# fc64x8.net
KiCad netlist of a schematic drawn in EAGLE
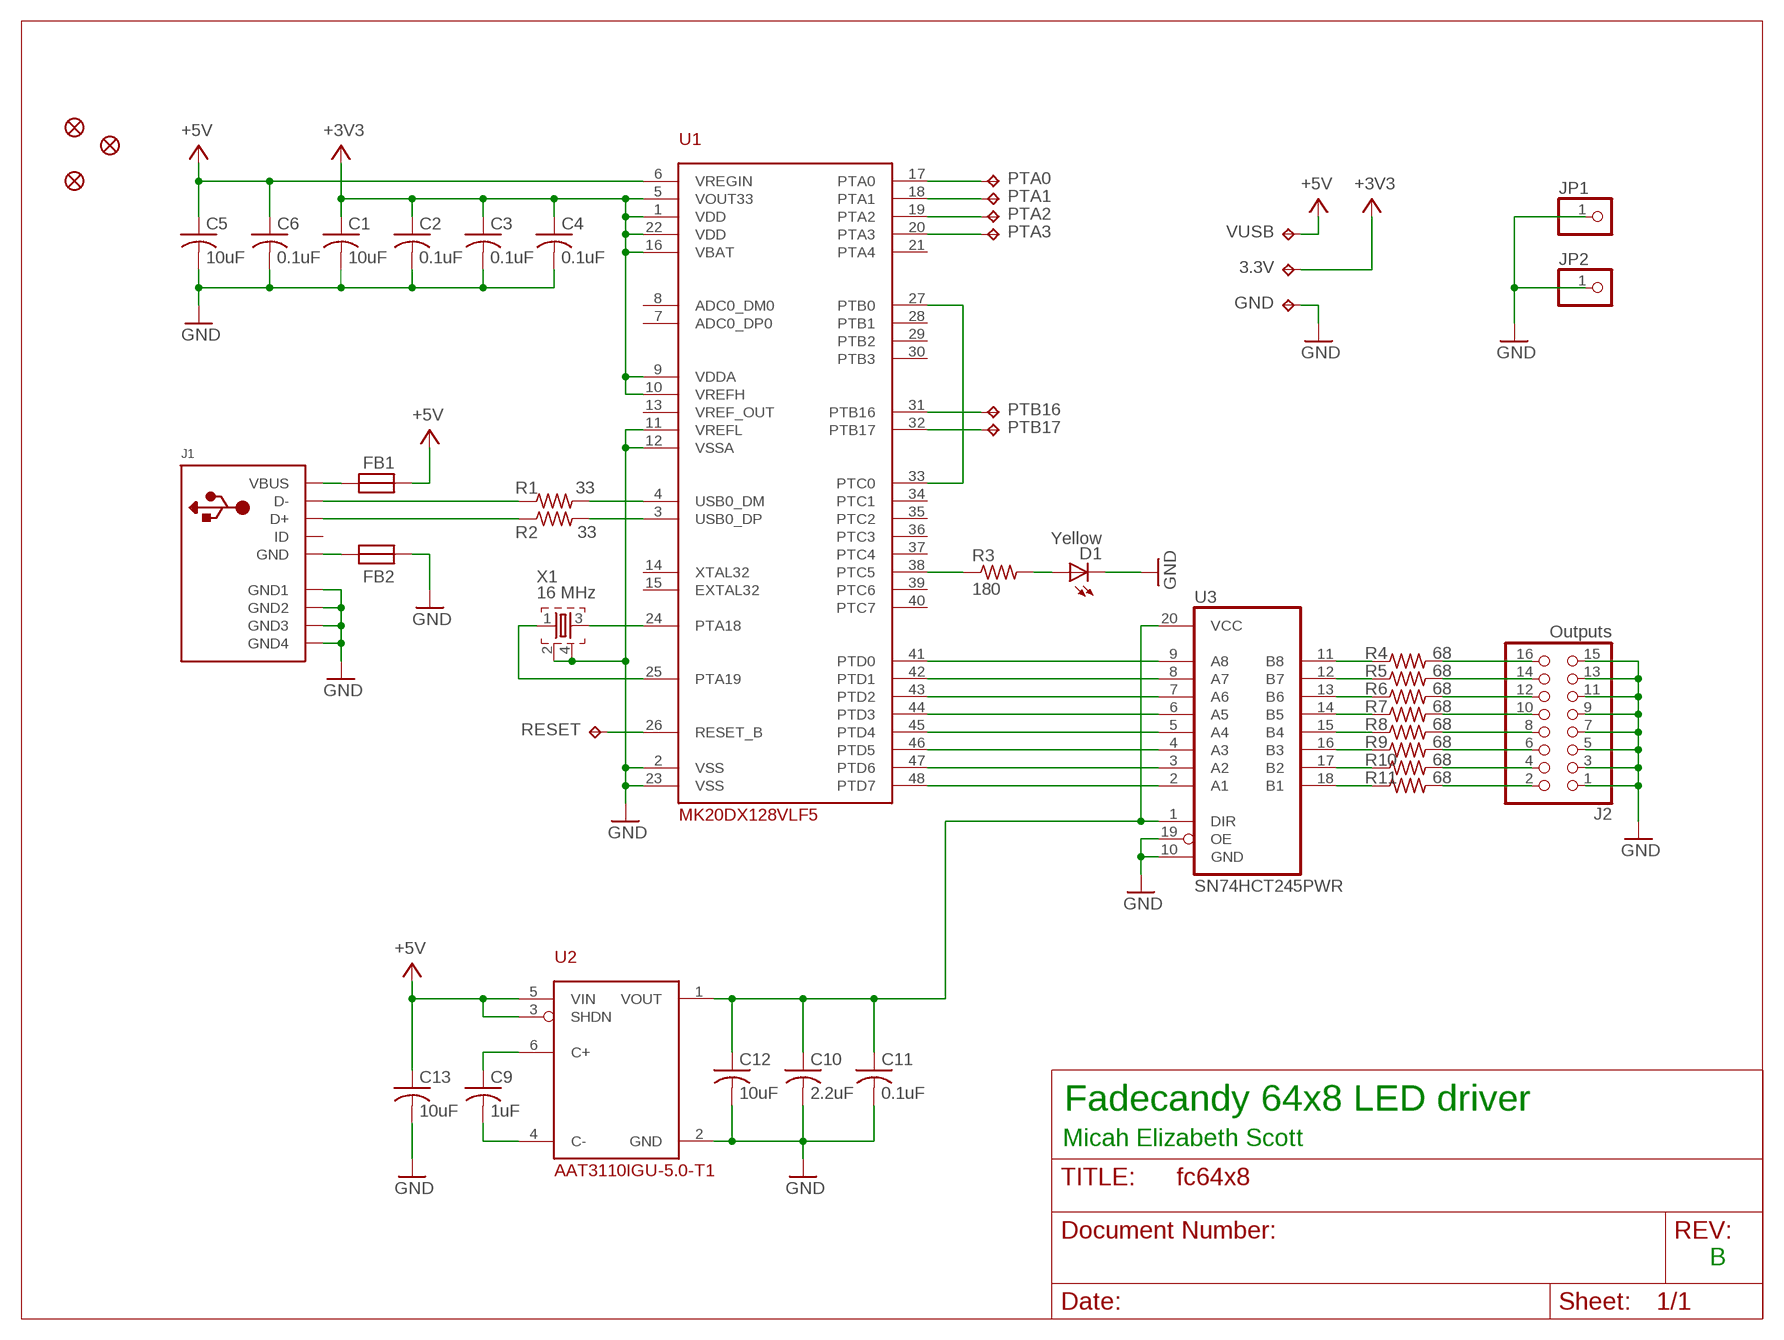
[diagram p0: schematic, sheet 1]

(export (version "E")
  (design (tool "Eeschema 10.0.6"))
  (components
    (comp (ref "3.3V")
      (value "TPTP18SQ")
      (footprint "eagle-import:TP18SQ")
      (libsource (lib "eagle-import") (part "TPTP18SQ"))
    )
    (comp (ref "C1")
      (value "10uF")
      (footprint "eagle-import:0805")
      (libsource (lib "eagle-import") (part "C-US0805/NO-OUTLINE"))
    )
    (comp (ref "C2")
      (value "0.1uF")
      (footprint "eagle-import:0805")
      (libsource (lib "eagle-import") (part "C-US0805/NO-OUTLINE"))
    )
    (comp (ref "C3")
      (value "0.1uF")
      (footprint "eagle-import:0805")
      (libsource (lib "eagle-import") (part "C-US0805/NO-OUTLINE"))
    )
    (comp (ref "C4")
      (value "0.1uF")
      (footprint "eagle-import:0805")
      (libsource (lib "eagle-import") (part "C-US0805/NO-OUTLINE"))
    )
    (comp (ref "C5")
      (value "10uF")
      (footprint "eagle-import:0805")
      (libsource (lib "eagle-import") (part "C-US0805/NO-OUTLINE"))
    )
    (comp (ref "C6")
      (value "0.1uF")
      (footprint "eagle-import:0805")
      (libsource (lib "eagle-import") (part "C-US0805/NO-OUTLINE"))
    )
    (comp (ref "C9")
      (value "1uF")
      (footprint "eagle-import:0805")
      (libsource (lib "eagle-import") (part "C-US0805/NO-OUTLINE"))
    )
    (comp (ref "C10")
      (value "2.2uF")
      (footprint "eagle-import:0805")
      (libsource (lib "eagle-import") (part "C-US0805/NO-OUTLINE"))
    )
    (comp (ref "C11")
      (value "0.1uF")
      (footprint "eagle-import:0805")
      (libsource (lib "eagle-import") (part "C-US0805/NO-OUTLINE"))
    )
    (comp (ref "C12")
      (value "10uF")
      (footprint "eagle-import:0805")
      (libsource (lib "eagle-import") (part "C-US0805/NO-OUTLINE"))
    )
    (comp (ref "C13")
      (value "10uF")
      (footprint "eagle-import:0805")
      (libsource (lib "eagle-import") (part "C-US0805/NO-OUTLINE"))
    )
    (comp (ref "D1")
      (value "Yellow")
      (footprint "eagle-import:CHIP-LED0805")
      (libsource (lib "eagle-import") (part "LEDCHIP-LED0805"))
    )
    (comp (ref "FB1")
      (value "FB0805/NO-OUTLINE")
      (footprint "eagle-import:0805")
      (libsource (lib "eagle-import") (part "FB0805/NO-OUTLINE"))
    )
    (comp (ref "FB2")
      (value "FB0805/NO-OUTLINE")
      (footprint "eagle-import:0805")
      (libsource (lib "eagle-import") (part "FB0805/NO-OUTLINE"))
    )
    (comp (ref "FID1")
      (value "FIDUCIAL\"\"")
      (footprint "eagle-import:FIDUCIAL_1MM")
      (libsource (lib "eagle-import") (part "FIDUCIAL{dblquote}{dblquote}"))
    )
    (comp (ref "FID2")
      (value "FIDUCIAL\"\"")
      (footprint "eagle-import:FIDUCIAL_1MM")
      (libsource (lib "eagle-import") (part "FIDUCIAL{dblquote}{dblquote}"))
    )
    (comp (ref "FID3")
      (value "FIDUCIAL\"\"")
      (footprint "eagle-import:FIDUCIAL_1MM")
      (libsource (lib "eagle-import") (part "FIDUCIAL{dblquote}{dblquote}"))
    )
    (comp (ref "GND")
      (value "TPTP18SQ")
      (footprint "eagle-import:TP18SQ")
      (libsource (lib "eagle-import") (part "TPTP18SQ"))
    )
    (comp (ref "J1")
      (value "USBMINIB")
      (footprint "eagle-import:USB-MINIB")
      (libsource (lib "eagle-import") (part "USBMINIB"))
    )
    (comp (ref "J2")
      (value "Outputs")
      (footprint "eagle-import:2X08")
      (libsource (lib "eagle-import") (part "PINHD-2X8"))
    )
    (comp (ref "JP1")
      (value "PINHD-1X1")
      (footprint "eagle-import:1X01")
      (libsource (lib "eagle-import") (part "PINHD-1X1"))
    )
    (comp (ref "JP2")
      (value "PINHD-1X1")
      (footprint "eagle-import:1X01")
      (libsource (lib "eagle-import") (part "PINHD-1X1"))
    )
    (comp (ref "PTA0")
      (value "TPTP18SQ")
      (footprint "eagle-import:TP18SQ")
      (libsource (lib "eagle-import") (part "TPTP18SQ"))
    )
    (comp (ref "PTA1")
      (value "TPTP18SQ")
      (footprint "eagle-import:TP18SQ")
      (libsource (lib "eagle-import") (part "TPTP18SQ"))
    )
    (comp (ref "PTA2")
      (value "TPTP18SQ")
      (footprint "eagle-import:TP18SQ")
      (libsource (lib "eagle-import") (part "TPTP18SQ"))
    )
    (comp (ref "PTA3")
      (value "TPTP18SQ")
      (footprint "eagle-import:TP18SQ")
      (libsource (lib "eagle-import") (part "TPTP18SQ"))
    )
    (comp (ref "PTB16")
      (value "TPTP18SQ")
      (footprint "eagle-import:TP18SQ")
      (libsource (lib "eagle-import") (part "TPTP18SQ"))
    )
    (comp (ref "PTB17")
      (value "TPTP18SQ")
      (footprint "eagle-import:TP18SQ")
      (libsource (lib "eagle-import") (part "TPTP18SQ"))
    )
    (comp (ref "R1")
      (value "33")
      (footprint "eagle-import:0805")
      (libsource (lib "eagle-import") (part "R-US_0805/NO-OUTLINE"))
    )
    (comp (ref "R2")
      (value "33")
      (footprint "eagle-import:0805")
      (libsource (lib "eagle-import") (part "R-US_0805/NO-OUTLINE"))
    )
    (comp (ref "R3")
      (value "180")
      (footprint "eagle-import:0805")
      (libsource (lib "eagle-import") (part "R-US_0805/NO-OUTLINE"))
    )
    (comp (ref "R4")
      (value "68")
      (footprint "eagle-import:0805")
      (libsource (lib "eagle-import") (part "R-US_0805/NO-OUTLINE"))
    )
    (comp (ref "R5")
      (value "68")
      (footprint "eagle-import:0805")
      (libsource (lib "eagle-import") (part "R-US_0805/NO-OUTLINE"))
    )
    (comp (ref "R6")
      (value "68")
      (footprint "eagle-import:0805")
      (libsource (lib "eagle-import") (part "R-US_0805/NO-OUTLINE"))
    )
    (comp (ref "R7")
      (value "68")
      (footprint "eagle-import:0805")
      (libsource (lib "eagle-import") (part "R-US_0805/NO-OUTLINE"))
    )
    (comp (ref "R8")
      (value "68")
      (footprint "eagle-import:0805")
      (libsource (lib "eagle-import") (part "R-US_0805/NO-OUTLINE"))
    )
    (comp (ref "R9")
      (value "68")
      (footprint "eagle-import:0805")
      (libsource (lib "eagle-import") (part "R-US_0805/NO-OUTLINE"))
    )
    (comp (ref "R10")
      (value "68")
      (footprint "eagle-import:0805")
      (libsource (lib "eagle-import") (part "R-US_0805/NO-OUTLINE"))
    )
    (comp (ref "R11")
      (value "68")
      (footprint "eagle-import:0805")
      (libsource (lib "eagle-import") (part "R-US_0805/NO-OUTLINE"))
    )
    (comp (ref "RESET")
      (value "TPTP18SQ")
      (footprint "eagle-import:TP18SQ")
      (libsource (lib "eagle-import") (part "TPTP18SQ"))
    )
    (comp (ref "U1")
      (value "MK20DX128VLF5")
      (footprint "eagle-import:LQFP48")
      (libsource (lib "eagle-import") (part "MK20DX128VLF5"))
    )
    (comp (ref "U2")
      (value "AAT3110IGU-5.0-T1")
      (footprint "eagle-import:SOT23-6L")
      (libsource (lib "eagle-import") (part "AAT3110"))
    )
    (comp (ref "U3")
      (value "SN74HCT245PWR")
      (footprint "eagle-import:TSSOP20")
      (libsource (lib "eagle-import") (part "74245PW"))
    )
    (comp (ref "VUSB")
      (value "TPTP18SQ")
      (footprint "eagle-import:TP18SQ")
      (libsource (lib "eagle-import") (part "TPTP18SQ"))
    )
    (comp (ref "X1")
      (value "16 MHz")
      (footprint "eagle-import:TSX-3225")
      (libsource (lib "eagle-import") (part "TSX-32250"))
    )
  )
  (nets
    (net (code "1") (name "+3V3") (class "Default")
      (node (ref "3.3V") (pin "TP") (pinfunction "TP_TP") (pintype "input"))
      (node (ref "C1") (pin "1") (pinfunction "1_1") (pintype "passive"))
      (node (ref "C2") (pin "1") (pinfunction "1_1") (pintype "passive"))
      (node (ref "C3") (pin "1") (pinfunction "1_1") (pintype "passive"))
      (node (ref "C4") (pin "1") (pinfunction "1_1") (pintype "passive"))
      (node (ref "U1") (pin "1") (pinfunction "VDD_1") (pintype "bidirectional"))
      (node (ref "U1") (pin "10") (pinfunction "VREFH_10") (pintype "bidirectional"))
      (node (ref "U1") (pin "16") (pinfunction "VBAT_16") (pintype "bidirectional"))
      (node (ref "U1") (pin "22") (pinfunction "VDD_22") (pintype "bidirectional"))
      (node (ref "U1") (pin "5") (pinfunction "VOUT33_5") (pintype "bidirectional"))
      (node (ref "U1") (pin "9") (pinfunction "VDDA_9") (pintype "bidirectional"))
    )
    (net (code "2") (name "+5V") (class "Default")
      (node (ref "C13") (pin "1") (pinfunction "1_1") (pintype "passive"))
      (node (ref "C5") (pin "1") (pinfunction "1_1") (pintype "passive"))
      (node (ref "C6") (pin "1") (pinfunction "1_1") (pintype "passive"))
      (node (ref "FB1") (pin "2") (pinfunction "P$2_2") (pintype "bidirectional"))
      (node (ref "U1") (pin "6") (pinfunction "VREGIN_6") (pintype "bidirectional"))
      (node (ref "U2") (pin "3") (pinfunction "SHDN_3") (pintype "bidirectional"))
      (node (ref "U2") (pin "5") (pinfunction "VIN_5") (pintype "bidirectional"))
      (node (ref "VUSB") (pin "TP") (pinfunction "TP_TP") (pintype "input"))
    )
    (net (code "3") (name "GND") (class "Default")
      (node (ref "C1") (pin "2") (pinfunction "2_2") (pintype "passive"))
      (node (ref "C10") (pin "2") (pinfunction "2_2") (pintype "passive"))
      (node (ref "C11") (pin "2") (pinfunction "2_2") (pintype "passive"))
      (node (ref "C12") (pin "2") (pinfunction "2_2") (pintype "passive"))
      (node (ref "C13") (pin "2") (pinfunction "2_2") (pintype "passive"))
      (node (ref "C2") (pin "2") (pinfunction "2_2") (pintype "passive"))
      (node (ref "C3") (pin "2") (pinfunction "2_2") (pintype "passive"))
      (node (ref "C4") (pin "2") (pinfunction "2_2") (pintype "passive"))
      (node (ref "C5") (pin "2") (pinfunction "2_2") (pintype "passive"))
      (node (ref "C6") (pin "2") (pinfunction "2_2") (pintype "passive"))
      (node (ref "D1") (pin "C") (pinfunction "C_C") (pintype "passive"))
      (node (ref "FB2") (pin "2") (pinfunction "P$2_2") (pintype "bidirectional"))
      (node (ref "GND") (pin "TP") (pinfunction "TP_TP") (pintype "input"))
      (node (ref "J1") (pin "GND1") (pinfunction "GND1_GND1") (pintype "power_in"))
      (node (ref "J1") (pin "GND2") (pinfunction "GND2_GND2") (pintype "power_in"))
      (node (ref "J1") (pin "GND3") (pinfunction "GND3_GND3") (pintype "power_in"))
      (node (ref "J1") (pin "GND4") (pinfunction "GND4_GND4") (pintype "power_in"))
      (node (ref "J2") (pin "1") (pinfunction "1_1") (pintype "passive"))
      (node (ref "J2") (pin "11") (pinfunction "11_11") (pintype "passive"))
      (node (ref "J2") (pin "13") (pinfunction "13_13") (pintype "passive"))
      (node (ref "J2") (pin "15") (pinfunction "15_15") (pintype "passive"))
      (node (ref "J2") (pin "3") (pinfunction "3_3") (pintype "passive"))
      (node (ref "J2") (pin "5") (pinfunction "5_5") (pintype "passive"))
      (node (ref "J2") (pin "7") (pinfunction "7_7") (pintype "passive"))
      (node (ref "J2") (pin "9") (pinfunction "9_9") (pintype "passive"))
      (node (ref "JP1") (pin "1") (pinfunction "1_1") (pintype "passive"))
      (node (ref "JP2") (pin "1") (pinfunction "1_1") (pintype "passive"))
      (node (ref "U1") (pin "11") (pinfunction "VREFL_11") (pintype "bidirectional"))
      (node (ref "U1") (pin "12") (pinfunction "VSSA_12") (pintype "bidirectional"))
      (node (ref "U1") (pin "2") (pinfunction "VSS_2") (pintype "bidirectional"))
      (node (ref "U1") (pin "23") (pinfunction "VSS_23") (pintype "bidirectional"))
      (node (ref "U2") (pin "2") (pinfunction "GND_2") (pintype "bidirectional"))
      (node (ref "U3") (pin "10") (pinfunction "GND_10") (pintype "bidirectional"))
      (node (ref "U3") (pin "19") (pinfunction "OE_19") (pintype "input"))
      (node (ref "X1") (pin "2") (pinfunction "2_2") (pintype "passive"))
      (node (ref "X1") (pin "4") (pinfunction "4_4") (pintype "passive"))
    )
    (net (code "4") (name "Net-(D1-PadA)") (class "Default")
      (node (ref "D1") (pin "A") (pinfunction "A_A") (pintype "passive"))
      (node (ref "R3") (pin "2") (pinfunction "2_2") (pintype "passive"))
    )
    (net (code "5") (name "Net-(FB1-P$1)") (class "Default")
      (node (ref "FB1") (pin "1") (pinfunction "P$1_1") (pintype "bidirectional"))
      (node (ref "J1") (pin "VBUS") (pinfunction "VBUS_VBUS") (pintype "power_in"))
    )
    (net (code "6") (name "Net-(FB2-P$1)") (class "Default")
      (node (ref "FB2") (pin "1") (pinfunction "P$1_1") (pintype "bidirectional"))
      (node (ref "J1") (pin "GND") (pinfunction "GND_GND") (pintype "power_in"))
    )
    (net (code "7") (name "Net-(J1-PadD+)") (class "Default")
      (node (ref "J1") (pin "D+") (pinfunction "D+_D+") (pintype "bidirectional"))
      (node (ref "R2") (pin "1") (pinfunction "1_1") (pintype "passive"))
    )
    (net (code "8") (name "Net-(J1-PadD-)") (class "Default")
      (node (ref "J1") (pin "D-") (pinfunction "D-_D-") (pintype "bidirectional"))
      (node (ref "R1") (pin "1") (pinfunction "1_1") (pintype "passive"))
    )
    (net (code "9") (name "Net-(J2-Pad2)") (class "Default")
      (node (ref "J2") (pin "2") (pinfunction "2_2") (pintype "passive"))
      (node (ref "R11") (pin "2") (pinfunction "2_2") (pintype "passive"))
    )
    (net (code "10") (name "Net-(J2-Pad4)") (class "Default")
      (node (ref "J2") (pin "4") (pinfunction "4_4") (pintype "passive"))
      (node (ref "R10") (pin "2") (pinfunction "2_2") (pintype "passive"))
    )
    (net (code "11") (name "Net-(J2-Pad6)") (class "Default")
      (node (ref "J2") (pin "6") (pinfunction "6_6") (pintype "passive"))
      (node (ref "R9") (pin "2") (pinfunction "2_2") (pintype "passive"))
    )
    (net (code "12") (name "Net-(J2-Pad8)") (class "Default")
      (node (ref "J2") (pin "8") (pinfunction "8_8") (pintype "passive"))
      (node (ref "R8") (pin "2") (pinfunction "2_2") (pintype "passive"))
    )
    (net (code "13") (name "Net-(J2-Pad10)") (class "Default")
      (node (ref "J2") (pin "10") (pinfunction "10_10") (pintype "passive"))
      (node (ref "R7") (pin "2") (pinfunction "2_2") (pintype "passive"))
    )
    (net (code "14") (name "Net-(J2-Pad12)") (class "Default")
      (node (ref "J2") (pin "12") (pinfunction "12_12") (pintype "passive"))
      (node (ref "R6") (pin "2") (pinfunction "2_2") (pintype "passive"))
    )
    (net (code "15") (name "Net-(J2-Pad14)") (class "Default")
      (node (ref "J2") (pin "14") (pinfunction "14_14") (pintype "passive"))
      (node (ref "R5") (pin "2") (pinfunction "2_2") (pintype "passive"))
    )
    (net (code "16") (name "Net-(J2-Pad16)") (class "Default")
      (node (ref "J2") (pin "16") (pinfunction "16_16") (pintype "passive"))
      (node (ref "R4") (pin "2") (pinfunction "2_2") (pintype "passive"))
    )
    (net (code "17") (name "Net-(U1-PTA0)") (class "Default")
      (node (ref "PTA0") (pin "TP") (pinfunction "TP_TP") (pintype "input"))
      (node (ref "U1") (pin "17") (pinfunction "PTA0_17") (pintype "bidirectional"))
    )
    (net (code "18") (name "Net-(U1-PTA1)") (class "Default")
      (node (ref "PTA1") (pin "TP") (pinfunction "TP_TP") (pintype "input"))
      (node (ref "U1") (pin "18") (pinfunction "PTA1_18") (pintype "bidirectional"))
    )
    (net (code "19") (name "Net-(U1-PTA2)") (class "Default")
      (node (ref "PTA2") (pin "TP") (pinfunction "TP_TP") (pintype "input"))
      (node (ref "U1") (pin "19") (pinfunction "PTA2_19") (pintype "bidirectional"))
    )
    (net (code "20") (name "Net-(U1-PTA3)") (class "Default")
      (node (ref "PTA3") (pin "TP") (pinfunction "TP_TP") (pintype "input"))
      (node (ref "U1") (pin "20") (pinfunction "PTA3_20") (pintype "bidirectional"))
    )
    (net (code "21") (name "Net-(U1-PTA18)") (class "Default")
      (node (ref "U1") (pin "24") (pinfunction "PTA18_24") (pintype "bidirectional"))
      (node (ref "X1") (pin "3") (pinfunction "3_3") (pintype "passive"))
    )
    (net (code "22") (name "Net-(U1-PTA19)") (class "Default")
      (node (ref "U1") (pin "25") (pinfunction "PTA19_25") (pintype "bidirectional"))
      (node (ref "X1") (pin "1") (pinfunction "1_1") (pintype "passive"))
    )
    (net (code "23") (name "Net-(U1-PTB0)") (class "Default")
      (node (ref "U1") (pin "27") (pinfunction "PTB0_27") (pintype "bidirectional"))
      (node (ref "U1") (pin "33") (pinfunction "PTC0_33") (pintype "bidirectional"))
    )
    (net (code "24") (name "Net-(U1-PTB16)") (class "Default")
      (node (ref "PTB16") (pin "TP") (pinfunction "TP_TP") (pintype "input"))
      (node (ref "U1") (pin "31") (pinfunction "PTB16_31") (pintype "bidirectional"))
    )
    (net (code "25") (name "Net-(U1-PTB17)") (class "Default")
      (node (ref "PTB17") (pin "TP") (pinfunction "TP_TP") (pintype "input"))
      (node (ref "U1") (pin "32") (pinfunction "PTB17_32") (pintype "bidirectional"))
    )
    (net (code "26") (name "Net-(U1-PTC5)") (class "Default")
      (node (ref "R3") (pin "1") (pinfunction "1_1") (pintype "passive"))
      (node (ref "U1") (pin "38") (pinfunction "PTC5_38") (pintype "bidirectional"))
    )
    (net (code "27") (name "Net-(U1-PTD0)") (class "Default")
      (node (ref "U1") (pin "41") (pinfunction "PTD0_41") (pintype "bidirectional"))
      (node (ref "U3") (pin "9") (pinfunction "A8_9") (pintype "bidirectional"))
    )
    (net (code "28") (name "Net-(U1-PTD1)") (class "Default")
      (node (ref "U1") (pin "42") (pinfunction "PTD1_42") (pintype "bidirectional"))
      (node (ref "U3") (pin "8") (pinfunction "A7_8") (pintype "bidirectional"))
    )
    (net (code "29") (name "Net-(U1-PTD2)") (class "Default")
      (node (ref "U1") (pin "43") (pinfunction "PTD2_43") (pintype "bidirectional"))
      (node (ref "U3") (pin "7") (pinfunction "A6_7") (pintype "bidirectional"))
    )
    (net (code "30") (name "Net-(U1-PTD3)") (class "Default")
      (node (ref "U1") (pin "44") (pinfunction "PTD3_44") (pintype "bidirectional"))
      (node (ref "U3") (pin "6") (pinfunction "A5_6") (pintype "bidirectional"))
    )
    (net (code "31") (name "Net-(U1-PTD4)") (class "Default")
      (node (ref "U1") (pin "45") (pinfunction "PTD4_45") (pintype "bidirectional"))
      (node (ref "U3") (pin "5") (pinfunction "A4_5") (pintype "bidirectional"))
    )
    (net (code "32") (name "Net-(U1-PTD5)") (class "Default")
      (node (ref "U1") (pin "46") (pinfunction "PTD5_46") (pintype "bidirectional"))
      (node (ref "U3") (pin "4") (pinfunction "A3_4") (pintype "bidirectional"))
    )
    (net (code "33") (name "Net-(U1-PTD6)") (class "Default")
      (node (ref "U1") (pin "47") (pinfunction "PTD6_47") (pintype "bidirectional"))
      (node (ref "U3") (pin "3") (pinfunction "A2_3") (pintype "bidirectional"))
    )
    (net (code "34") (name "Net-(U1-PTD7)") (class "Default")
      (node (ref "U1") (pin "48") (pinfunction "PTD7_48") (pintype "bidirectional"))
      (node (ref "U3") (pin "2") (pinfunction "A1_2") (pintype "bidirectional"))
    )
    (net (code "35") (name "Net-(U1-RESET_B)") (class "Default")
      (node (ref "RESET") (pin "TP") (pinfunction "TP_TP") (pintype "input"))
      (node (ref "U1") (pin "26") (pinfunction "RESET_B_26") (pintype "bidirectional"))
    )
    (net (code "36") (name "Net-(U1-USB0_DM)") (class "Default")
      (node (ref "R1") (pin "2") (pinfunction "2_2") (pintype "passive"))
      (node (ref "U1") (pin "4") (pinfunction "USB0_DM_4") (pintype "bidirectional"))
    )
    (net (code "37") (name "Net-(U1-USB0_DP)") (class "Default")
      (node (ref "R2") (pin "2") (pinfunction "2_2") (pintype "passive"))
      (node (ref "U1") (pin "3") (pinfunction "USB0_DP_3") (pintype "bidirectional"))
    )
    (net (code "38") (name "Net-(U2-C+)") (class "Default")
      (node (ref "C9") (pin "1") (pinfunction "1_1") (pintype "passive"))
      (node (ref "U2") (pin "6") (pinfunction "C+_6") (pintype "bidirectional"))
    )
    (net (code "39") (name "Net-(U2-C-)") (class "Default")
      (node (ref "C9") (pin "2") (pinfunction "2_2") (pintype "passive"))
      (node (ref "U2") (pin "4") (pinfunction "C-_4") (pintype "bidirectional"))
    )
    (net (code "40") (name "Net-(U2-VOUT)") (class "Default")
      (node (ref "C10") (pin "1") (pinfunction "1_1") (pintype "passive"))
      (node (ref "C11") (pin "1") (pinfunction "1_1") (pintype "passive"))
      (node (ref "C12") (pin "1") (pinfunction "1_1") (pintype "passive"))
      (node (ref "U2") (pin "1") (pinfunction "VOUT_1") (pintype "bidirectional"))
      (node (ref "U3") (pin "1") (pinfunction "DIR_1") (pintype "input"))
      (node (ref "U3") (pin "20") (pinfunction "VCC_20") (pintype "bidirectional"))
    )
    (net (code "41") (name "Net-(U3-B1)") (class "Default")
      (node (ref "R11") (pin "1") (pinfunction "1_1") (pintype "passive"))
      (node (ref "U3") (pin "18") (pinfunction "B1_18") (pintype "bidirectional"))
    )
    (net (code "42") (name "Net-(U3-B2)") (class "Default")
      (node (ref "R10") (pin "1") (pinfunction "1_1") (pintype "passive"))
      (node (ref "U3") (pin "17") (pinfunction "B2_17") (pintype "bidirectional"))
    )
    (net (code "43") (name "Net-(U3-B3)") (class "Default")
      (node (ref "R9") (pin "1") (pinfunction "1_1") (pintype "passive"))
      (node (ref "U3") (pin "16") (pinfunction "B3_16") (pintype "bidirectional"))
    )
    (net (code "44") (name "Net-(U3-B4)") (class "Default")
      (node (ref "R8") (pin "1") (pinfunction "1_1") (pintype "passive"))
      (node (ref "U3") (pin "15") (pinfunction "B4_15") (pintype "bidirectional"))
    )
    (net (code "45") (name "Net-(U3-B5)") (class "Default")
      (node (ref "R7") (pin "1") (pinfunction "1_1") (pintype "passive"))
      (node (ref "U3") (pin "14") (pinfunction "B5_14") (pintype "bidirectional"))
    )
    (net (code "46") (name "Net-(U3-B6)") (class "Default")
      (node (ref "R6") (pin "1") (pinfunction "1_1") (pintype "passive"))
      (node (ref "U3") (pin "13") (pinfunction "B6_13") (pintype "bidirectional"))
    )
    (net (code "47") (name "Net-(U3-B7)") (class "Default")
      (node (ref "R5") (pin "1") (pinfunction "1_1") (pintype "passive"))
      (node (ref "U3") (pin "12") (pinfunction "B7_12") (pintype "bidirectional"))
    )
    (net (code "48") (name "Net-(U3-B8)") (class "Default")
      (node (ref "R4") (pin "1") (pinfunction "1_1") (pintype "passive"))
      (node (ref "U3") (pin "11") (pinfunction "B8_11") (pintype "bidirectional"))
    )
    (net (code "49") (name "unconnected-(J1-PadID)") (class "Default")
      (node (ref "J1") (pin "ID") (pinfunction "ID_ID") (pintype "bidirectional"))
    )
    (net (code "50") (name "unconnected-(U1-ADC0_DM0-Pad8)") (class "Default")
      (node (ref "U1") (pin "8") (pinfunction "ADC0_DM0_8") (pintype "bidirectional"))
    )
    (net (code "51") (name "unconnected-(U1-ADC0_DP0-Pad7)") (class "Default")
      (node (ref "U1") (pin "7") (pinfunction "ADC0_DP0_7") (pintype "bidirectional"))
    )
    (net (code "52") (name "unconnected-(U1-EXTAL32-Pad15)") (class "Default")
      (node (ref "U1") (pin "15") (pinfunction "EXTAL32_15") (pintype "bidirectional"))
    )
    (net (code "53") (name "unconnected-(U1-PTA4-Pad21)") (class "Default")
      (node (ref "U1") (pin "21") (pinfunction "PTA4_21") (pintype "bidirectional"))
    )
    (net (code "54") (name "unconnected-(U1-PTB1-Pad28)") (class "Default")
      (node (ref "U1") (pin "28") (pinfunction "PTB1_28") (pintype "bidirectional"))
    )
    (net (code "55") (name "unconnected-(U1-PTB2-Pad29)") (class "Default")
      (node (ref "U1") (pin "29") (pinfunction "PTB2_29") (pintype "bidirectional"))
    )
    (net (code "56") (name "unconnected-(U1-PTB3-Pad30)") (class "Default")
      (node (ref "U1") (pin "30") (pinfunction "PTB3_30") (pintype "bidirectional"))
    )
    (net (code "57") (name "unconnected-(U1-PTC1-Pad34)") (class "Default")
      (node (ref "U1") (pin "34") (pinfunction "PTC1_34") (pintype "bidirectional"))
    )
    (net (code "58") (name "unconnected-(U1-PTC2-Pad35)") (class "Default")
      (node (ref "U1") (pin "35") (pinfunction "PTC2_35") (pintype "bidirectional"))
    )
    (net (code "59") (name "unconnected-(U1-PTC3-Pad36)") (class "Default")
      (node (ref "U1") (pin "36") (pinfunction "PTC3_36") (pintype "bidirectional"))
    )
    (net (code "60") (name "unconnected-(U1-PTC4-Pad37)") (class "Default")
      (node (ref "U1") (pin "37") (pinfunction "PTC4_37") (pintype "bidirectional"))
    )
    (net (code "61") (name "unconnected-(U1-PTC6-Pad39)") (class "Default")
      (node (ref "U1") (pin "39") (pinfunction "PTC6_39") (pintype "bidirectional"))
    )
    (net (code "62") (name "unconnected-(U1-PTC7-Pad40)") (class "Default")
      (node (ref "U1") (pin "40") (pinfunction "PTC7_40") (pintype "bidirectional"))
    )
    (net (code "63") (name "unconnected-(U1-VREF_OUT-Pad13)") (class "Default")
      (node (ref "U1") (pin "13") (pinfunction "VREF_OUT_13") (pintype "bidirectional"))
    )
    (net (code "64") (name "unconnected-(U1-XTAL32-Pad14)") (class "Default")
      (node (ref "U1") (pin "14") (pinfunction "XTAL32_14") (pintype "bidirectional"))
    )
  )
)
